# Main.net
KiCad netlist of a schematic drawn in Altium Designer
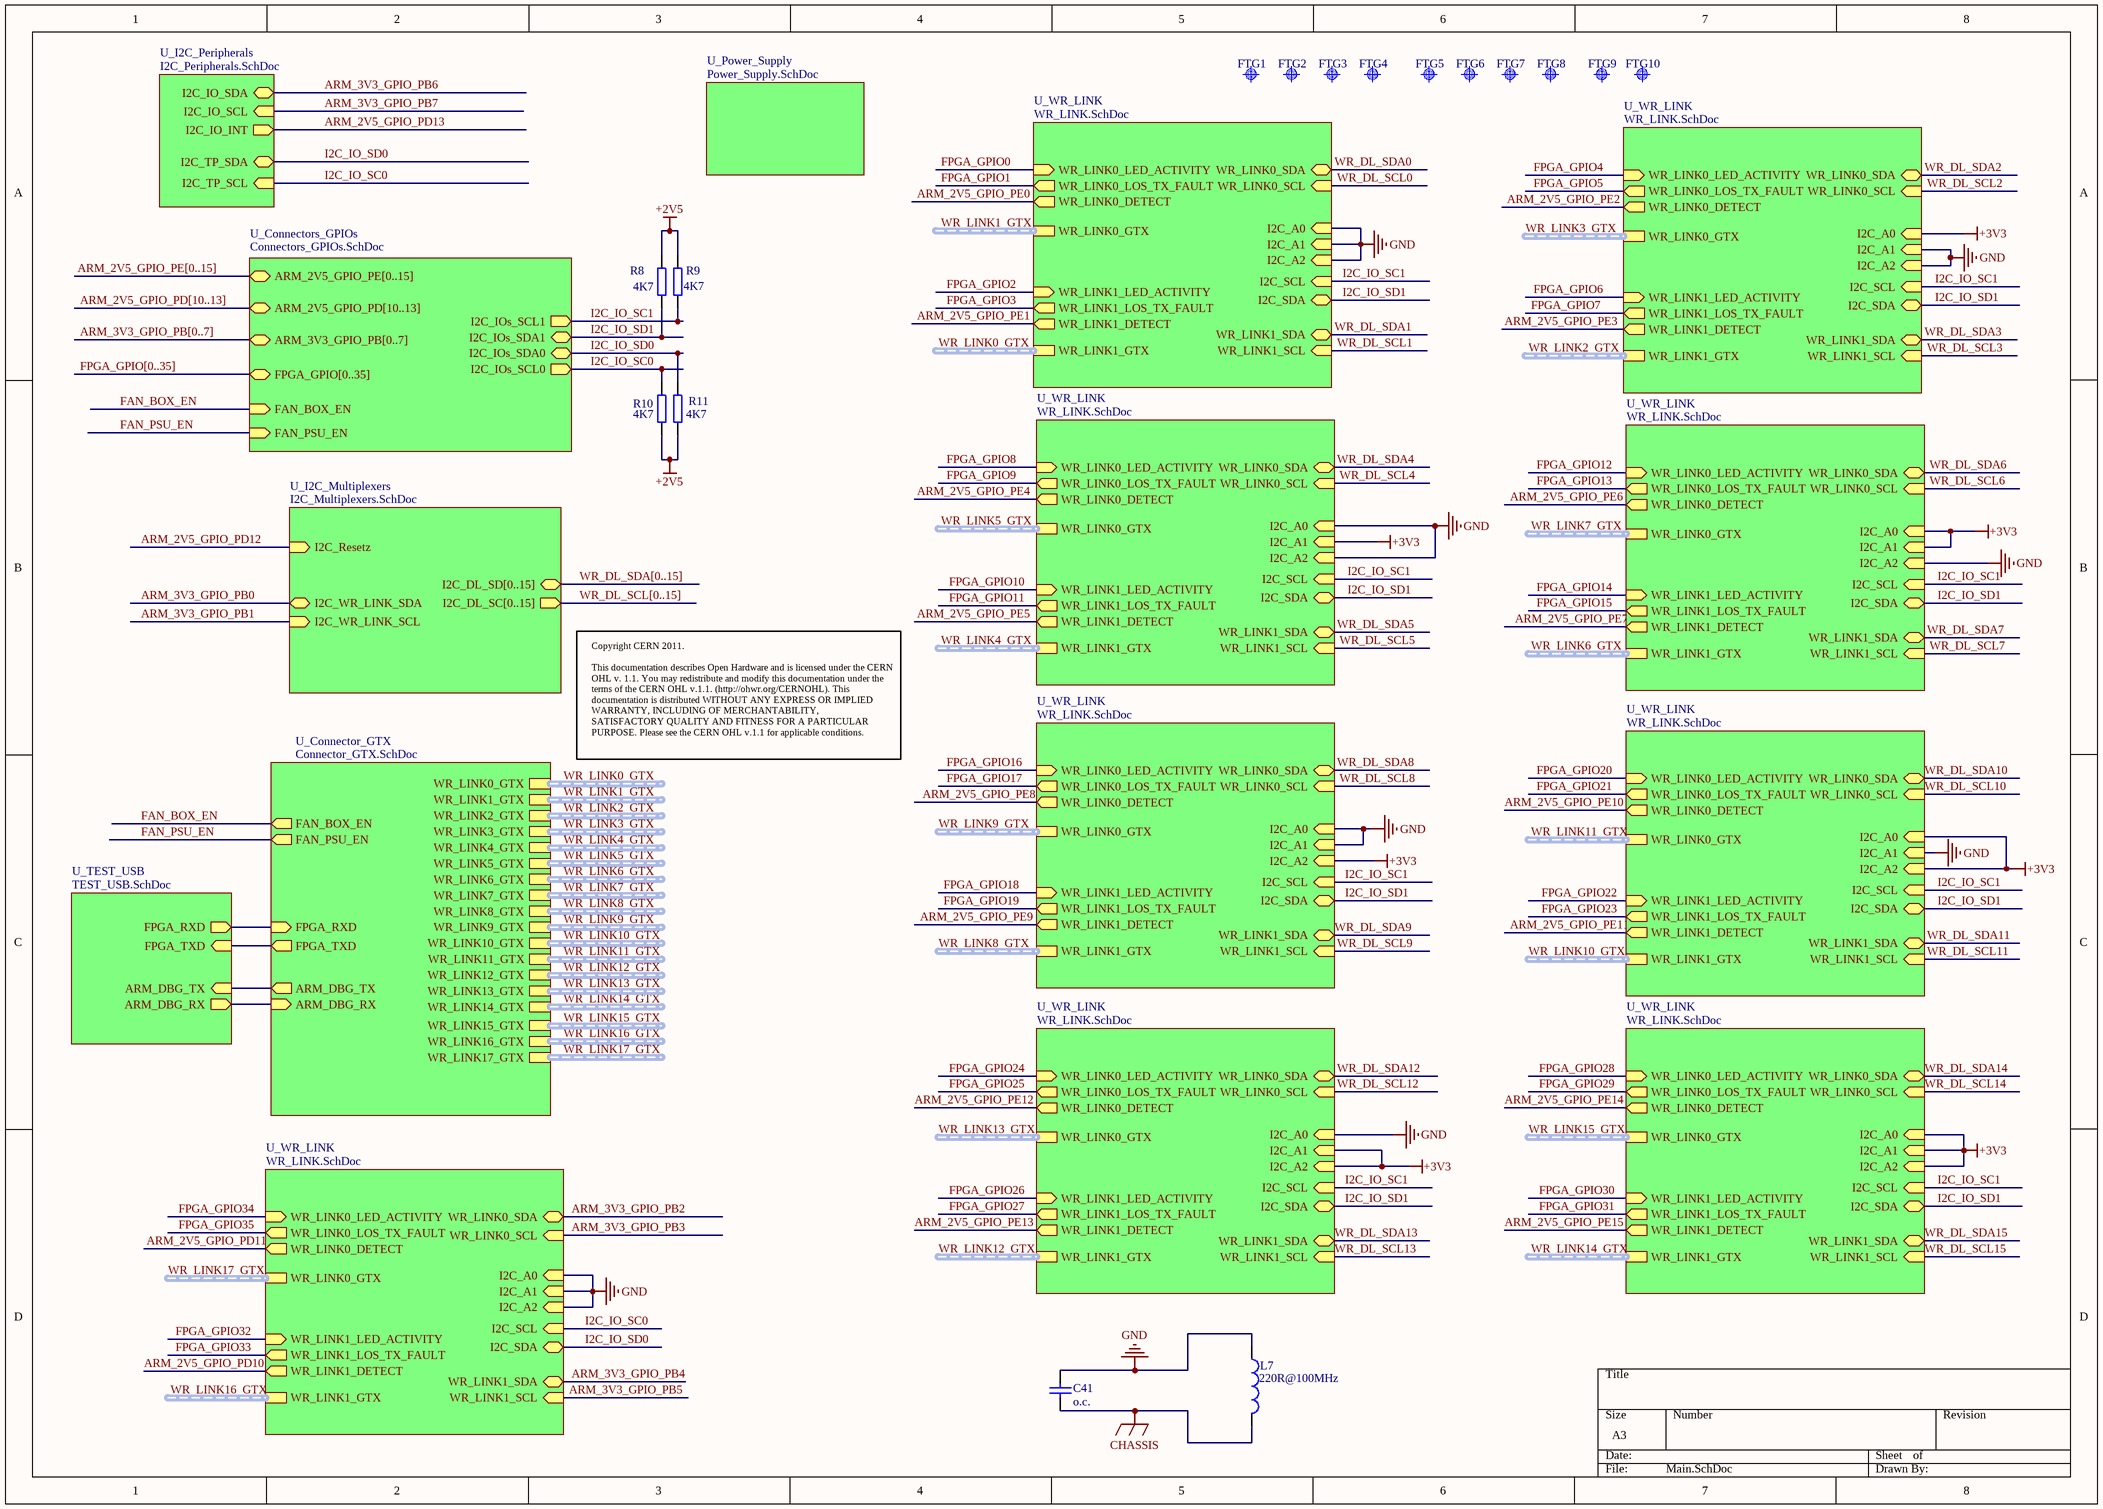
[diagram p0: Main.SchDoc]

(export (version "E")
  (design (tool "Eeschema 10.0.6"))
  (components
    (comp (ref "C41")
      (value "o.c.")
      (footprint "CC1608-0603")
      (description "Capacitor")
      (fields
        (field (name "TOLERANCE") "±10%")
        (field (name "VOLTAGE") "16V")
        (field (name "PUBLISHER") "Altium Limited")
      )
      (libsource (lib "wr_switch") (part "Cap"))
    )
    (comp (ref "FTG1")
      (value "Use only in PCB")
      (footprint "FIDUCIAL_TOP_S100-200")
      (description "Fiducial Target")
      (fields (field (name "PART NUMBER") "FIDUCIAL_TARGET_S100-200") (field (name "AUTHOR") "CERN DEM JLC"))
      (libsource (lib "wr_switch") (part "Fiducial Target"))
    )
    (comp (ref "FTG2")
      (value "Use only in PCB")
      (footprint "FIDUCIAL_TOP_S100-200")
      (description "Fiducial Target")
      (fields (field (name "PART NUMBER") "FIDUCIAL_TARGET_S100-200") (field (name "AUTHOR") "CERN DEM JLC"))
      (libsource (lib "wr_switch") (part "Fiducial Target"))
    )
    (comp (ref "FTG3")
      (value "Use only in PCB")
      (footprint "FIDUCIAL_TOP_S100-200")
      (description "Fiducial Target")
      (fields (field (name "PART NUMBER") "FIDUCIAL_TARGET_S100-200") (field (name "AUTHOR") "CERN DEM JLC"))
      (libsource (lib "wr_switch") (part "Fiducial Target"))
    )
    (comp (ref "FTG4")
      (value "Use only in PCB")
      (footprint "FIDUCIAL_TOP_S100-200")
      (description "Fiducial Target")
      (fields (field (name "PART NUMBER") "FIDUCIAL_TARGET_S100-200") (field (name "AUTHOR") "CERN DEM JLC"))
      (libsource (lib "wr_switch") (part "Fiducial Target"))
    )
    (comp (ref "FTG5")
      (value "Use only in PCB")
      (footprint "FIDUCIAL_TOP_S100-200")
      (description "Fiducial Target")
      (fields (field (name "PART NUMBER") "FIDUCIAL_TARGET_S100-200") (field (name "AUTHOR") "CERN DEM JLC"))
      (libsource (lib "wr_switch") (part "Fiducial Target"))
    )
    (comp (ref "FTG6")
      (value "Use only in PCB")
      (footprint "FIDUCIAL_TOP_S100-200")
      (description "Fiducial Target")
      (fields (field (name "PART NUMBER") "FIDUCIAL_TARGET_S100-200") (field (name "AUTHOR") "CERN DEM JLC"))
      (libsource (lib "wr_switch") (part "Fiducial Target"))
    )
    (comp (ref "FTG7")
      (value "Use only in PCB")
      (footprint "FIDUCIAL_TOP_S100-200")
      (description "Fiducial Target")
      (fields (field (name "PART NUMBER") "FIDUCIAL_TARGET_S100-200") (field (name "AUTHOR") "CERN DEM JLC"))
      (libsource (lib "wr_switch") (part "Fiducial Target"))
    )
    (comp (ref "FTG8")
      (value "Use only in PCB")
      (footprint "FIDUCIAL_TOP_S100-200")
      (description "Fiducial Target")
      (fields (field (name "PART NUMBER") "FIDUCIAL_TARGET_S100-200") (field (name "AUTHOR") "CERN DEM JLC"))
      (libsource (lib "wr_switch") (part "Fiducial Target"))
    )
    (comp (ref "FTG9")
      (value "Use only in PCB")
      (footprint "FIDUCIAL_TOP_S100-200")
      (description "Fiducial Target")
      (fields (field (name "PART NUMBER") "FIDUCIAL_TARGET_S100-200") (field (name "AUTHOR") "CERN DEM JLC"))
      (libsource (lib "wr_switch") (part "Fiducial Target"))
    )
    (comp (ref "FTG10")
      (value "Use only in PCB")
      (footprint "FIDUCIAL_TOP_S100-200")
      (description "Fiducial Target")
      (fields (field (name "PART NUMBER") "FIDUCIAL_TARGET_S100-200") (field (name "AUTHOR") "CERN DEM JLC"))
      (libsource (lib "wr_switch") (part "Fiducial Target"))
    )
    (comp (ref "L7")
      (value "220R@100MHz Ferrite Bead")
      (footprint "0603")
      (description "ferrite bead")
      (fields (field (name "IMPEDANCE") "220R@100MHz"))
      (libsource (lib "wr_switch") (part "L_FERRITE_BEAD"))
    )
    (comp (ref "R8")
      (value "4K7")
      (footprint "0603")
      (description "SMD Resistor")
      (fields (field (name "TOLERANCE") "±1%"))
      (libsource (lib "wr_switch") (part "RES_SMD"))
    )
    (comp (ref "R9")
      (value "4K7")
      (footprint "0603")
      (description "SMD Resistor")
      (fields (field (name "TOLERANCE") "±1%"))
      (libsource (lib "wr_switch") (part "RES_SMD"))
    )
    (comp (ref "R10")
      (value "4K7")
      (footprint "0603")
      (description "SMD Resistor")
      (fields (field (name "TOLERANCE") "±1%"))
      (libsource (lib "wr_switch") (part "RES_SMD"))
    )
    (comp (ref "R11")
      (value "4K7")
      (footprint "0603")
      (description "SMD Resistor")
      (fields (field (name "TOLERANCE") "±1%"))
      (libsource (lib "wr_switch") (part "RES_SMD"))
    )
  )
  (nets
    (net (code "19") (name "+2V5") (class "Default")
      (node (ref "R10") (pin "2") (pinfunction "2_2") (pintype "passive"))
      (node (ref "R11") (pin "1") (pinfunction "1_1") (pintype "passive"))
      (node (ref "R8") (pin "2") (pinfunction "2_2") (pintype "passive"))
      (node (ref "R9") (pin "1") (pinfunction "1_1") (pintype "passive"))
    )
    (net (code "101") (name "/I2C_IO_SC0") (class "Default")
      (node (ref "R10") (pin "1") (pinfunction "1_1") (pintype "passive"))
    )
    (net (code "102") (name "/I2C_IO_SC1") (class "Default")
      (node (ref "R9") (pin "2") (pinfunction "2_2") (pintype "passive"))
    )
    (net (code "103") (name "/I2C_IO_SD0") (class "Default")
      (node (ref "R11") (pin "2") (pinfunction "2_2") (pintype "passive"))
    )
    (net (code "104") (name "/I2C_IO_SD1") (class "Default")
      (node (ref "R8") (pin "1") (pinfunction "1_1") (pintype "passive"))
    )
    (net (code "184") (name "CHASSIS") (class "Default")
      (node (ref "C41") (pin "1") (pinfunction "1_1") (pintype "passive"))
      (node (ref "L7") (pin "2") (pinfunction "2_2") (pintype "passive"))
    )
    (net (code "185") (name "GND") (class "Default")
      (node (ref "C41") (pin "2") (pinfunction "2_2") (pintype "passive"))
      (node (ref "L7") (pin "1") (pinfunction "1_1") (pintype "passive"))
    )
  )
)
